# lp_redir.net
KiCad netlist of a schematic drawn in EAGLE
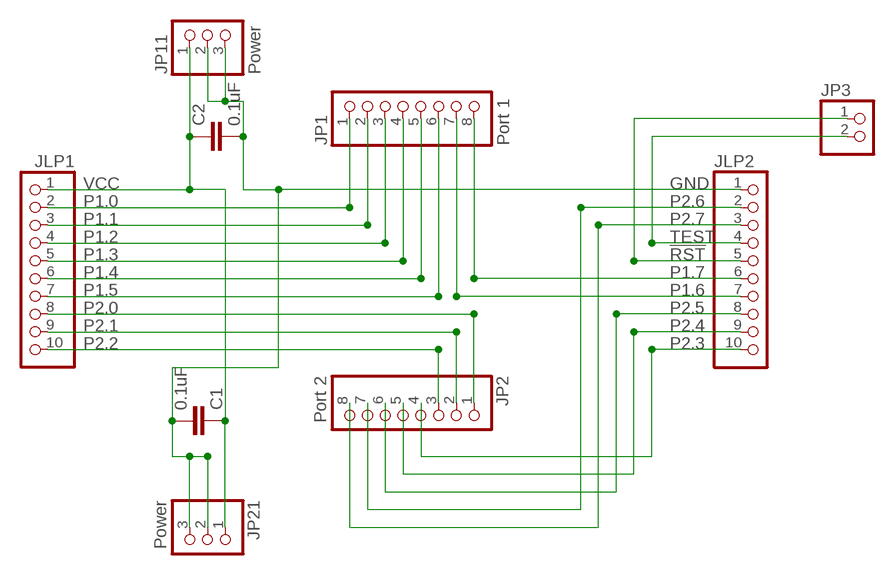
[diagram p0: schematic, sheet 1]

(export (version "E")
  (design (tool "Eeschema 10.0.6"))
  (components
    (comp (ref "C1")
      (value "0.1uF")
      (footprint "eagle-import:C025-025X050")
      (libsource (lib "eagle-import") (part "C-EU025-025X050"))
    )
    (comp (ref "C2")
      (value "0.1uF")
      (footprint "eagle-import:C025-025X050")
      (libsource (lib "eagle-import") (part "C-EU025-025X050"))
    )
    (comp (ref "JLP1")
      (value "PH1X10OCT076")
      (footprint "eagle-import:PH1X10OCT76")
      (libsource (lib "eagle-import") (part "PH1X10OCT076"))
    )
    (comp (ref "JLP2")
      (value "PH1X10OCT076")
      (footprint "eagle-import:PH1X10OCT76")
      (libsource (lib "eagle-import") (part "PH1X10OCT076"))
    )
    (comp (ref "JP1")
      (value "Port 1")
      (footprint "eagle-import:1X08")
      (libsource (lib "eagle-import") (part "PINHD-1X8"))
    )
    (comp (ref "JP2")
      (value "Port 2")
      (footprint "eagle-import:1X08")
      (libsource (lib "eagle-import") (part "PINHD-1X8"))
    )
    (comp (ref "JP3")
      (value "PINHD-1X2")
      (footprint "eagle-import:1X02")
      (libsource (lib "eagle-import") (part "PINHD-1X2"))
    )
    (comp (ref "JP11")
      (value "Power")
      (footprint "eagle-import:1X03")
      (libsource (lib "eagle-import") (part "PINHD-1X3"))
    )
    (comp (ref "JP21")
      (value "Power")
      (footprint "eagle-import:1X03")
      (libsource (lib "eagle-import") (part "PINHD-1X3"))
    )
  )
  (nets
    (net (code "1") (name "/GND") (class "Default")
      (node (ref "C1") (pin "2") (pinfunction "2_2") (pintype "passive"))
      (node (ref "C2") (pin "2") (pinfunction "2_2") (pintype "passive"))
      (node (ref "JLP2") (pin "1") (pinfunction "1_1") (pintype "passive"))
      (node (ref "JP11") (pin "2") (pinfunction "2_2") (pintype "passive"))
      (node (ref "JP11") (pin "3") (pinfunction "3_3") (pintype "passive"))
      (node (ref "JP21") (pin "2") (pinfunction "2_2") (pintype "passive"))
      (node (ref "JP21") (pin "3") (pinfunction "3_3") (pintype "passive"))
    )
    (net (code "2") (name "/P1.0") (class "Default")
      (node (ref "JLP1") (pin "2") (pinfunction "2_2") (pintype "passive"))
      (node (ref "JP1") (pin "1") (pinfunction "1_1") (pintype "passive"))
    )
    (net (code "3") (name "/P1.1") (class "Default")
      (node (ref "JLP1") (pin "3") (pinfunction "3_3") (pintype "passive"))
      (node (ref "JP1") (pin "2") (pinfunction "2_2") (pintype "passive"))
    )
    (net (code "4") (name "/P1.2") (class "Default")
      (node (ref "JLP1") (pin "4") (pinfunction "4_4") (pintype "passive"))
      (node (ref "JP1") (pin "3") (pinfunction "3_3") (pintype "passive"))
    )
    (net (code "5") (name "/P1.3") (class "Default")
      (node (ref "JLP1") (pin "5") (pinfunction "5_5") (pintype "passive"))
      (node (ref "JP1") (pin "4") (pinfunction "4_4") (pintype "passive"))
    )
    (net (code "6") (name "/P1.4") (class "Default")
      (node (ref "JLP1") (pin "6") (pinfunction "6_6") (pintype "passive"))
      (node (ref "JP1") (pin "5") (pinfunction "5_5") (pintype "passive"))
    )
    (net (code "7") (name "/P1.5") (class "Default")
      (node (ref "JLP1") (pin "7") (pinfunction "7_7") (pintype "passive"))
      (node (ref "JP1") (pin "6") (pinfunction "6_6") (pintype "passive"))
    )
    (net (code "8") (name "/P1.6") (class "Default")
      (node (ref "JLP2") (pin "7") (pinfunction "7_7") (pintype "passive"))
      (node (ref "JP1") (pin "7") (pinfunction "7_7") (pintype "passive"))
    )
    (net (code "9") (name "/P1.7") (class "Default")
      (node (ref "JLP2") (pin "6") (pinfunction "6_6") (pintype "passive"))
      (node (ref "JP1") (pin "8") (pinfunction "8_8") (pintype "passive"))
    )
    (net (code "10") (name "/P2.0") (class "Default")
      (node (ref "JLP1") (pin "8") (pinfunction "8_8") (pintype "passive"))
      (node (ref "JP2") (pin "1") (pinfunction "1_1") (pintype "passive"))
    )
    (net (code "11") (name "/P2.1") (class "Default")
      (node (ref "JLP1") (pin "9") (pinfunction "9_9") (pintype "passive"))
      (node (ref "JP2") (pin "2") (pinfunction "2_2") (pintype "passive"))
    )
    (net (code "12") (name "/P2.2") (class "Default")
      (node (ref "JLP1") (pin "10") (pinfunction "10_10") (pintype "passive"))
      (node (ref "JP2") (pin "3") (pinfunction "3_3") (pintype "passive"))
    )
    (net (code "13") (name "/P2.3") (class "Default")
      (node (ref "JLP2") (pin "10") (pinfunction "10_10") (pintype "passive"))
      (node (ref "JP2") (pin "4") (pinfunction "4_4") (pintype "passive"))
    )
    (net (code "14") (name "/P2.4") (class "Default")
      (node (ref "JLP2") (pin "9") (pinfunction "9_9") (pintype "passive"))
      (node (ref "JP2") (pin "5") (pinfunction "5_5") (pintype "passive"))
    )
    (net (code "15") (name "/P2.5") (class "Default")
      (node (ref "JLP2") (pin "8") (pinfunction "8_8") (pintype "passive"))
      (node (ref "JP2") (pin "6") (pinfunction "6_6") (pintype "passive"))
    )
    (net (code "16") (name "/P2.6") (class "Default")
      (node (ref "JLP2") (pin "2") (pinfunction "2_2") (pintype "passive"))
      (node (ref "JP2") (pin "7") (pinfunction "7_7") (pintype "passive"))
    )
    (net (code "17") (name "/P2.7") (class "Default")
      (node (ref "JLP2") (pin "3") (pinfunction "3_3") (pintype "passive"))
      (node (ref "JP2") (pin "8") (pinfunction "8_8") (pintype "passive"))
    )
    (net (code "18") (name "/TEST") (class "Default")
      (node (ref "JLP2") (pin "4") (pinfunction "4_4") (pintype "passive"))
      (node (ref "JP3") (pin "2") (pinfunction "2_2") (pintype "passive"))
    )
    (net (code "19") (name "/VCC") (class "Default")
      (node (ref "C1") (pin "1") (pinfunction "1_1") (pintype "passive"))
      (node (ref "C2") (pin "1") (pinfunction "1_1") (pintype "passive"))
      (node (ref "JLP1") (pin "1") (pinfunction "1_1") (pintype "passive"))
      (node (ref "JP11") (pin "1") (pinfunction "1_1") (pintype "passive"))
      (node (ref "JP21") (pin "1") (pinfunction "1_1") (pintype "passive"))
    )
    (net (code "20") (name "/~{RST}") (class "Default")
      (node (ref "JLP2") (pin "5") (pinfunction "5_5") (pintype "passive"))
      (node (ref "JP3") (pin "1") (pinfunction "1_1") (pintype "passive"))
    )
  )
)
